# BLELink.net
KiCad netlist of a schematic drawn in EAGLE
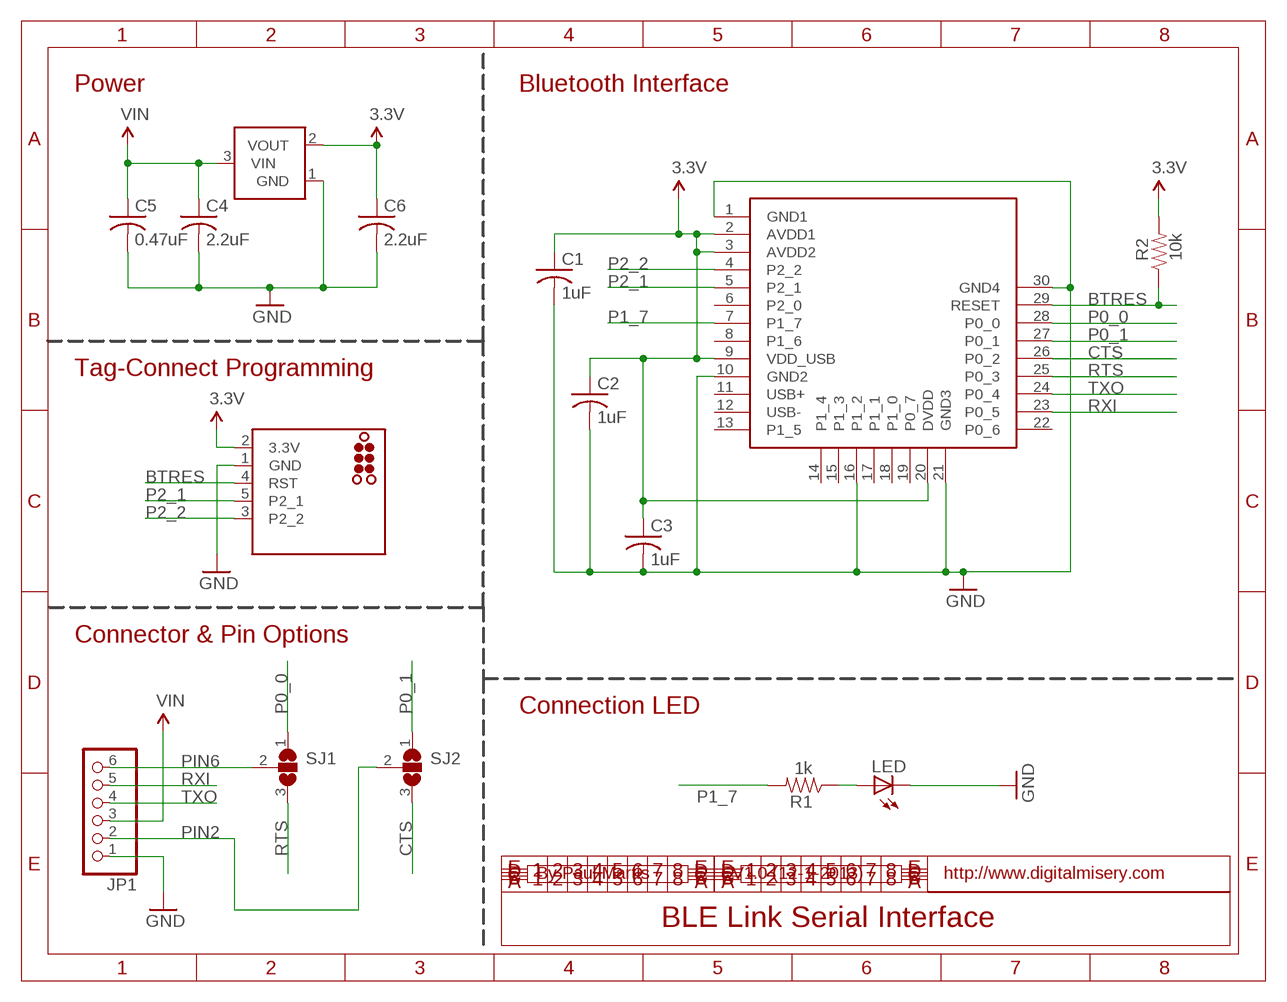
[diagram p0: schematic, sheet 1]

(export (version "E")
  (design (tool "Eeschema 10.0.6"))
  (components
    (comp (ref "C1")
      (value "1uF")
      (footprint "eagle-import:C0805K")
      (libsource (lib "eagle-import") (part "C-USC0805K"))
    )
    (comp (ref "C2")
      (value "1uF")
      (footprint "eagle-import:C0805K")
      (libsource (lib "eagle-import") (part "C-USC0805K"))
    )
    (comp (ref "C3")
      (value "1uF")
      (footprint "eagle-import:C0805K")
      (libsource (lib "eagle-import") (part "C-USC0805K"))
    )
    (comp (ref "C4")
      (value "2.2uF")
      (footprint "eagle-import:C0805K")
      (libsource (lib "eagle-import") (part "C-USC0805K"))
    )
    (comp (ref "C5")
      (value "0.47uF")
      (footprint "eagle-import:C0805K")
      (libsource (lib "eagle-import") (part "C-USC0805K"))
    )
    (comp (ref "C6")
      (value "2.2uF")
      (footprint "eagle-import:C0805K")
      (libsource (lib "eagle-import") (part "C-USC0805K"))
    )
    (comp (ref "J1")
      (value "TC2030-CC-DEBUGGER")
      (footprint "eagle-import:TC2030-MCP-NL")
      (libsource (lib "eagle-import") (part "TC2030-CC-DEBUGGER"))
    )
    (comp (ref "JP1")
      (value "PINHD-1X6CB")
      (footprint "eagle-import:1X06-CLEANBIG")
      (libsource (lib "eagle-import") (part "PINHD-1X6CB"))
    )
    (comp (ref "LED")
      (value "LEDCHIP-LED0805")
      (footprint "eagle-import:CHIP-LED0805")
      (libsource (lib "eagle-import") (part "LEDCHIP-LED0805"))
    )
    (comp (ref "R1")
      (value "1k")
      (footprint "eagle-import:0805")
      (libsource (lib "eagle-import") (part "RESISTOR0805-RES"))
    )
    (comp (ref "R2")
      (value "10k")
      (footprint "eagle-import:0805")
      (libsource (lib "eagle-import") (part "RESISTOR0805-RES"))
    )
    (comp (ref "SJ1")
      (value "SJ2W")
      (footprint "eagle-import:SJ_2")
      (libsource (lib "eagle-import") (part "SJ2W"))
    )
    (comp (ref "SJ2")
      (value "SJ2W")
      (footprint "eagle-import:SJ_2")
      (libsource (lib "eagle-import") (part "SJ2W"))
    )
    (comp (ref "U1")
      (value "MCP1700")
      (footprint "eagle-import:SOT23-3")
      (libsource (lib "eagle-import") (part "MCP1700"))
    )
    (comp (ref "U2")
      (value "BLE112-A")
      (footprint "eagle-import:BLE112-A")
      (libsource (lib "eagle-import") (part "BLE112-A"))
    )
  )
  (nets
    (net (code "1") (name "/BTRES") (class "Default")
      (node (ref "J1") (pin "4") (pinfunction "RST_4") (pintype "bidirectional"))
      (node (ref "R2") (pin "1") (pinfunction "1_1") (pintype "passive"))
      (node (ref "U2") (pin "29") (pinfunction "RESET_29") (pintype "bidirectional"))
    )
    (net (code "2") (name "/CTS") (class "Default")
      (node (ref "SJ2") (pin "3") (pinfunction "3_3") (pintype "passive"))
      (node (ref "U2") (pin "26") (pinfunction "P0_2_26") (pintype "bidirectional"))
    )
    (net (code "3") (name "/P0_0") (class "Default")
      (node (ref "SJ1") (pin "1") (pinfunction "1_1") (pintype "passive"))
      (node (ref "U2") (pin "28") (pinfunction "P0_0_28") (pintype "bidirectional"))
    )
    (net (code "4") (name "/P0_1") (class "Default")
      (node (ref "SJ2") (pin "1") (pinfunction "1_1") (pintype "passive"))
      (node (ref "U2") (pin "27") (pinfunction "P0_1_27") (pintype "bidirectional"))
    )
    (net (code "5") (name "/P1_7") (class "Default")
      (node (ref "R1") (pin "2") (pinfunction "2_2") (pintype "passive"))
      (node (ref "U2") (pin "7") (pinfunction "P1_7_7") (pintype "bidirectional"))
    )
    (net (code "6") (name "/P2_1") (class "Default")
      (node (ref "J1") (pin "5") (pinfunction "P2_1_5") (pintype "bidirectional"))
      (node (ref "U2") (pin "5") (pinfunction "P2_1_5") (pintype "bidirectional"))
    )
    (net (code "7") (name "/P2_2") (class "Default")
      (node (ref "J1") (pin "3") (pinfunction "P2_2_3") (pintype "bidirectional"))
      (node (ref "U2") (pin "4") (pinfunction "P2_2_4") (pintype "bidirectional"))
    )
    (net (code "8") (name "/PIN2") (class "Default")
      (node (ref "JP1") (pin "2") (pinfunction "2_2") (pintype "passive"))
      (node (ref "SJ2") (pin "2") (pinfunction "2_2") (pintype "passive"))
    )
    (net (code "9") (name "/PIN6") (class "Default")
      (node (ref "JP1") (pin "6") (pinfunction "6_6") (pintype "passive"))
      (node (ref "SJ1") (pin "2") (pinfunction "2_2") (pintype "passive"))
    )
    (net (code "10") (name "/RTS") (class "Default")
      (node (ref "SJ1") (pin "3") (pinfunction "3_3") (pintype "passive"))
      (node (ref "U2") (pin "25") (pinfunction "P0_3_25") (pintype "bidirectional"))
    )
    (net (code "11") (name "/RXI") (class "Default")
      (node (ref "JP1") (pin "5") (pinfunction "5_5") (pintype "passive"))
      (node (ref "U2") (pin "23") (pinfunction "P0_5_23") (pintype "bidirectional"))
    )
    (net (code "12") (name "/TXO") (class "Default")
      (node (ref "JP1") (pin "4") (pinfunction "4_4") (pintype "passive"))
      (node (ref "U2") (pin "24") (pinfunction "P0_4_24") (pintype "bidirectional"))
    )
    (net (code "13") (name "3.3V") (class "Default")
      (node (ref "C1") (pin "1") (pinfunction "1_1") (pintype "passive"))
      (node (ref "C2") (pin "1") (pinfunction "1_1") (pintype "passive"))
      (node (ref "C3") (pin "1") (pinfunction "1_1") (pintype "passive"))
      (node (ref "C6") (pin "1") (pinfunction "1_1") (pintype "passive"))
      (node (ref "J1") (pin "2") (pinfunction "3.3V_2") (pintype "power_in"))
      (node (ref "R2") (pin "2") (pinfunction "2_2") (pintype "passive"))
      (node (ref "U1") (pin "2") (pinfunction "VOUT_2") (pintype "power_in"))
      (node (ref "U2") (pin "2") (pinfunction "AVDD1_2") (pintype "bidirectional"))
      (node (ref "U2") (pin "20") (pinfunction "DVDD_20") (pintype "bidirectional"))
      (node (ref "U2") (pin "3") (pinfunction "AVDD2_3") (pintype "bidirectional"))
      (node (ref "U2") (pin "9") (pinfunction "VDD_USB_9") (pintype "bidirectional"))
    )
    (net (code "14") (name "GND") (class "Default")
      (node (ref "C1") (pin "2") (pinfunction "2_2") (pintype "passive"))
      (node (ref "C2") (pin "2") (pinfunction "2_2") (pintype "passive"))
      (node (ref "C3") (pin "2") (pinfunction "2_2") (pintype "passive"))
      (node (ref "C4") (pin "2") (pinfunction "2_2") (pintype "passive"))
      (node (ref "C5") (pin "2") (pinfunction "2_2") (pintype "passive"))
      (node (ref "C6") (pin "2") (pinfunction "2_2") (pintype "passive"))
      (node (ref "J1") (pin "1") (pinfunction "GND_1") (pintype "power_in"))
      (node (ref "JP1") (pin "1") (pinfunction "1_1") (pintype "passive"))
      (node (ref "LED") (pin "C") (pinfunction "C_C") (pintype "passive"))
      (node (ref "U1") (pin "1") (pinfunction "GND_1") (pintype "power_in"))
      (node (ref "U2") (pin "1") (pinfunction "GND1_1") (pintype "bidirectional"))
      (node (ref "U2") (pin "10") (pinfunction "GND2_10") (pintype "bidirectional"))
      (node (ref "U2") (pin "16") (pinfunction "P1_2_16") (pintype "bidirectional"))
      (node (ref "U2") (pin "21") (pinfunction "GND3_21") (pintype "bidirectional"))
      (node (ref "U2") (pin "30") (pinfunction "GND4_30") (pintype "bidirectional"))
    )
    (net (code "15") (name "Net-(LED-PadA)") (class "Default")
      (node (ref "LED") (pin "A") (pinfunction "A_A") (pintype "passive"))
      (node (ref "R1") (pin "1") (pinfunction "1_1") (pintype "passive"))
    )
    (net (code "16") (name "VIN") (class "Default")
      (node (ref "C4") (pin "1") (pinfunction "1_1") (pintype "passive"))
      (node (ref "C5") (pin "1") (pinfunction "1_1") (pintype "passive"))
      (node (ref "JP1") (pin "3") (pinfunction "3_3") (pintype "passive"))
      (node (ref "U1") (pin "3") (pinfunction "VIN_3") (pintype "power_in"))
    )
    (net (code "17") (name "unconnected-(U2-P0_6-Pad22)") (class "Default")
      (node (ref "U2") (pin "22") (pinfunction "P0_6_22") (pintype "bidirectional"))
    )
    (net (code "18") (name "unconnected-(U2-P0_7-Pad19)") (class "Default")
      (node (ref "U2") (pin "19") (pinfunction "P0_7_19") (pintype "bidirectional"))
    )
    (net (code "19") (name "unconnected-(U2-P1_0-Pad18)") (class "Default")
      (node (ref "U2") (pin "18") (pinfunction "P1_0_18") (pintype "bidirectional"))
    )
    (net (code "20") (name "unconnected-(U2-P1_1-Pad17)") (class "Default")
      (node (ref "U2") (pin "17") (pinfunction "P1_1_17") (pintype "bidirectional"))
    )
    (net (code "21") (name "unconnected-(U2-P1_3-Pad15)") (class "Default")
      (node (ref "U2") (pin "15") (pinfunction "P1_3_15") (pintype "bidirectional"))
    )
    (net (code "22") (name "unconnected-(U2-P1_4-Pad14)") (class "Default")
      (node (ref "U2") (pin "14") (pinfunction "P1_4_14") (pintype "bidirectional"))
    )
    (net (code "23") (name "unconnected-(U2-P1_5-Pad13)") (class "Default")
      (node (ref "U2") (pin "13") (pinfunction "P1_5_13") (pintype "bidirectional"))
    )
    (net (code "24") (name "unconnected-(U2-P1_6-Pad8)") (class "Default")
      (node (ref "U2") (pin "8") (pinfunction "P1_6_8") (pintype "bidirectional"))
    )
    (net (code "25") (name "unconnected-(U2-P2_0-Pad6)") (class "Default")
      (node (ref "U2") (pin "6") (pinfunction "P2_0_6") (pintype "bidirectional"))
    )
    (net (code "26") (name "unconnected-(U2-USB+-Pad11)") (class "Default")
      (node (ref "U2") (pin "11") (pinfunction "USB+_11") (pintype "bidirectional"))
    )
    (net (code "27") (name "unconnected-(U2-USB--Pad12)") (class "Default")
      (node (ref "U2") (pin "12") (pinfunction "USB-_12") (pintype "bidirectional"))
    )
  )
)
